# furby.net
KiCad netlist of a schematic drawn in EAGLE
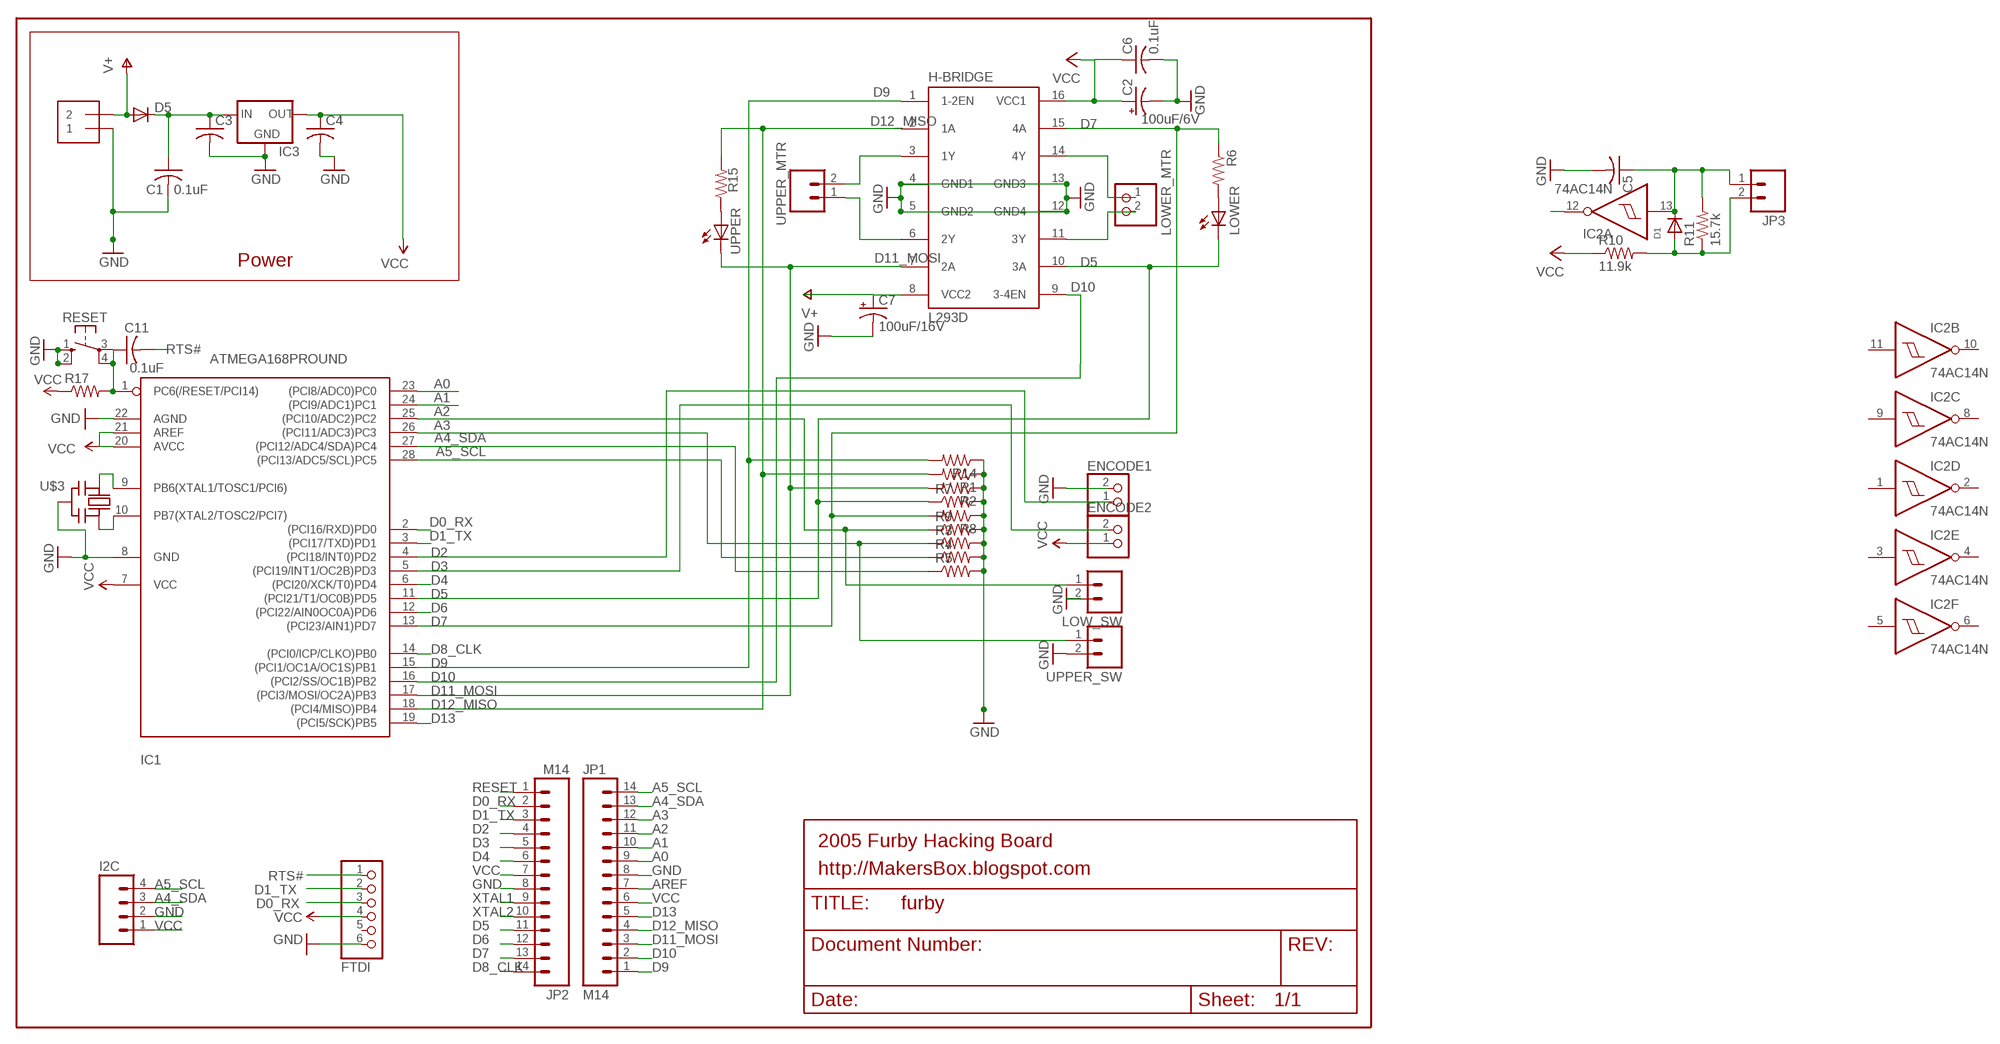
[diagram p0: schematic, sheet 1]

(export (version "E")
  (design (tool "Eeschema 10.0.6"))
  (components
    (comp (ref "C1")
      (value "0.1uF")
      (footprint "eagle-import:C025-025X050")
      (libsource (lib "eagle-import") (part "minimidi_C-US025-025X050"))
    )
    (comp (ref "C2")
      (value "100uF/6V")
      (footprint "eagle-import:E2,5-5")
      (libsource (lib "eagle-import") (part "CPOL-USE2.5-5"))
    )
    (comp (ref "C3")
      (value "C-US025-025X050")
      (footprint "eagle-import:C025-025X050")
      (libsource (lib "eagle-import") (part "C-US025-025X050"))
    )
    (comp (ref "C4")
      (value "C-US025-025X050")
      (footprint "eagle-import:C025-025X050")
      (libsource (lib "eagle-import") (part "C-US025-025X050"))
    )
    (comp (ref "C5")
      (value "C-US050-025X075")
      (footprint "eagle-import:C050-025X075")
      (libsource (lib "eagle-import") (part "C-US050-025X075"))
    )
    (comp (ref "C6")
      (value "0.1uF")
      (footprint "eagle-import:C025-025X050")
      (libsource (lib "eagle-import") (part "rcl-ez_C-US025-025X050"))
    )
    (comp (ref "C7")
      (value "100uF/16V")
      (footprint "eagle-import:E2,5-6")
      (libsource (lib "eagle-import") (part "CPOL-USE2.5-6"))
    )
    (comp (ref "C11")
      (value "0.1uF")
      (footprint "eagle-import:C025-025X050")
      (libsource (lib "eagle-import") (part "minimidi_C-US025-025X050"))
    )
    (comp (ref "D1")
      (value "DIODEDO-1N4148")
      (footprint "eagle-import:DO-1N4148")
      (libsource (lib "eagle-import") (part "DIODEDO-1N4148"))
    )
    (comp (ref "D5")
      (value "DIODE-D-5")
      (footprint "eagle-import:D-5")
      (libsource (lib "eagle-import") (part "DIODE-D-5"))
    )
    (comp (ref "ENCODE1")
      (value "JST_2PIN-THM")
      (footprint "eagle-import:JST-PH-2-THM")
      (libsource (lib "eagle-import") (part "JST_2PIN-THM"))
    )
    (comp (ref "ENCODE2")
      (value "JST_2PIN-THM")
      (footprint "eagle-import:JST-PH-2-THM")
      (libsource (lib "eagle-import") (part "JST_2PIN-THM"))
    )
    (comp (ref "FTDI")
      (value "FTDI")
      (footprint "eagle-import:1X06-CLEANBIG")
      (libsource (lib "eagle-import") (part "PINHD-1X6CB"))
    )
    (comp (ref "H-BRIDGE")
      (value "L293D")
      (footprint "eagle-import:DIL16")
      (libsource (lib "eagle-import") (part "L293E"))
    )
    (comp (ref "I2C")
      (value "M04PTH")
      (footprint "eagle-import:1X04")
      (libsource (lib "eagle-import") (part "M04PTH"))
    )
    (comp (ref "IC1")
      (value "ATMEGA168PROUND")
      (footprint "eagle-import:DIL28-3-ROUND")
      (libsource (lib "eagle-import") (part "ATMEGA168PROUND"))
    )
    (comp (ref "IC2")
      (value "74AC14N")
      (footprint "eagle-import:DIL14")
      (libsource (lib "eagle-import") (part "7414NAC"))
    )
    (comp (ref "IC3")
      (value "MCP1700INLINE")
      (footprint "eagle-import:TO92-INLINE")
      (libsource (lib "eagle-import") (part "MCP1700INLINE"))
    )
    (comp (ref "J1")
      (value "1X2-3.5MM")
      (footprint "eagle-import:1X2-3.5MM")
      (libsource (lib "eagle-import") (part "1X2-3.5MM"))
    )
    (comp (ref "JP1")
      (value "M14")
      (footprint "eagle-import:1X14")
      (libsource (lib "eagle-import") (part "M14"))
    )
    (comp (ref "JP2")
      (value "M14")
      (footprint "eagle-import:1X14")
      (libsource (lib "eagle-import") (part "M14"))
    )
    (comp (ref "JP3")
      (value "M02PTH")
      (footprint "eagle-import:1X02")
      (libsource (lib "eagle-import") (part "M02PTH"))
    )
    (comp (ref "LOWER")
      (value "LED3MM")
      (footprint "eagle-import:LED3MM")
      (libsource (lib "eagle-import") (part "LED3MM"))
    )
    (comp (ref "LOWER_MTR")
      (value "JST_2PIN-THM")
      (footprint "eagle-import:JST-PH-2-THM")
      (libsource (lib "eagle-import") (part "JST_2PIN-THM"))
    )
    (comp (ref "LOW_SW")
      (value "M02PTH")
      (footprint "eagle-import:1X02")
      (libsource (lib "eagle-import") (part "M02PTH"))
    )
    (comp (ref "R1")
      (value "R-US_0207/2V")
      (footprint "eagle-import:0207_2V")
      (libsource (lib "eagle-import") (part "R-US_0207/2V"))
    )
    (comp (ref "R2")
      (value "R-US_0207/2V")
      (footprint "eagle-import:0207_2V")
      (libsource (lib "eagle-import") (part "R-US_0207/2V"))
    )
    (comp (ref "R3")
      (value "R-US_0207/2V")
      (footprint "eagle-import:0207_2V")
      (libsource (lib "eagle-import") (part "R-US_0207/2V"))
    )
    (comp (ref "R4")
      (value "RESISTORPTH-1/6W")
      (footprint "eagle-import:1_6W-RES")
      (libsource (lib "eagle-import") (part "RESISTORPTH-1/6W"))
    )
    (comp (ref "R5")
      (value "RESISTORPTH-1/6W")
      (footprint "eagle-import:1_6W-RES")
      (libsource (lib "eagle-import") (part "RESISTORPTH-1/6W"))
    )
    (comp (ref "R6")
      (value "R-US_0207/2V")
      (footprint "eagle-import:0207_2V")
      (libsource (lib "eagle-import") (part "R-US_0207/2V"))
    )
    (comp (ref "R7")
      (value "R-US_0207/2V")
      (footprint "eagle-import:0207_2V")
      (libsource (lib "eagle-import") (part "R-US_0207/2V"))
    )
    (comp (ref "R8")
      (value "R-US_0207/2V")
      (footprint "eagle-import:0207_2V")
      (libsource (lib "eagle-import") (part "R-US_0207/2V"))
    )
    (comp (ref "R9")
      (value "R-US_0207/2V")
      (footprint "eagle-import:0207_2V")
      (libsource (lib "eagle-import") (part "R-US_0207/2V"))
    )
    (comp (ref "R10")
      (value "11.9k")
      (footprint "eagle-import:0204_7")
      (libsource (lib "eagle-import") (part "R-US_0204/7"))
    )
    (comp (ref "R11")
      (value "15.7k")
      (footprint "eagle-import:0204_7")
      (libsource (lib "eagle-import") (part "R-US_0204/7"))
    )
    (comp (ref "R14")
      (value "R-US_0207/2V")
      (footprint "eagle-import:0207_2V")
      (libsource (lib "eagle-import") (part "R-US_0207/2V"))
    )
    (comp (ref "R15")
      (value "R-US_0207/2V")
      (footprint "eagle-import:0207_2V")
      (libsource (lib "eagle-import") (part "R-US_0207/2V"))
    )
    (comp (ref "R17")
      (value "R-US_0207/2V")
      (footprint "eagle-import:0207_2V")
      (libsource (lib "eagle-import") (part "R-US_0207/2V"))
    )
    (comp (ref "RESET")
      (value "10-XX")
      (footprint "eagle-import:B3F-10XX")
      (libsource (lib "eagle-import") (part "10-XX"))
    )
    (comp (ref "U$3")
      (value "CERMOSCILL-THM")
      (footprint "eagle-import:CERM_OSC")
      (libsource (lib "eagle-import") (part "CERMOSCILL-THM"))
    )
    (comp (ref "UPPER")
      (value "LED3MM")
      (footprint "eagle-import:LED3MM")
      (libsource (lib "eagle-import") (part "LED3MM"))
    )
    (comp (ref "UPPER_MTR")
      (value "M02POLAR")
      (footprint "eagle-import:MOLEX-1X2")
      (libsource (lib "eagle-import") (part "M02POLAR"))
    )
    (comp (ref "UPPER_SW")
      (value "M02PTH")
      (footprint "eagle-import:1X02")
      (libsource (lib "eagle-import") (part "M02PTH"))
    )
  )
  (nets
    (net (code "1") (name "/A0") (class "Default")
      (node (ref "IC1") (pin "23") (pinfunction "(PCI8/ADC0)PC0_23") (pintype "bidirectional"))
      (node (ref "JP1") (pin "9") (pinfunction "9_9") (pintype "passive"))
    )
    (net (code "2") (name "/A1") (class "Default")
      (node (ref "IC1") (pin "24") (pinfunction "(PCI9/ADC1)PC1_24") (pintype "bidirectional"))
      (node (ref "JP1") (pin "10") (pinfunction "10_10") (pintype "passive"))
    )
    (net (code "3") (name "/A2") (class "Default")
      (node (ref "IC1") (pin "25") (pinfunction "(PCI10/ADC2)PC2_25") (pintype "bidirectional"))
      (node (ref "JP1") (pin "11") (pinfunction "11_11") (pintype "passive"))
      (node (ref "LOW_SW") (pin "1") (pinfunction "1_1") (pintype "passive"))
      (node (ref "R9") (pin "1") (pinfunction "1_1") (pintype "passive"))
    )
    (net (code "4") (name "/A3") (class "Default")
      (node (ref "IC1") (pin "26") (pinfunction "(PCI11/ADC3)PC3_26") (pintype "bidirectional"))
      (node (ref "JP1") (pin "12") (pinfunction "12_12") (pintype "passive"))
      (node (ref "R3") (pin "1") (pinfunction "1_1") (pintype "passive"))
      (node (ref "UPPER_SW") (pin "1") (pinfunction "1_1") (pintype "passive"))
    )
    (net (code "5") (name "/A4_SDA") (class "Default")
      (node (ref "I2C") (pin "3") (pinfunction "3_3") (pintype "passive"))
      (node (ref "IC1") (pin "27") (pinfunction "(PCI12/ADC4/SDA)PC4_27") (pintype "bidirectional"))
      (node (ref "JP1") (pin "13") (pinfunction "13_13") (pintype "passive"))
      (node (ref "R5") (pin "1") (pinfunction "1_1") (pintype "passive"))
    )
    (net (code "6") (name "/A5_SCL") (class "Default")
      (node (ref "I2C") (pin "4") (pinfunction "4_4") (pintype "passive"))
      (node (ref "IC1") (pin "28") (pinfunction "(PCI13/ADC5/SCL)PC5_28") (pintype "bidirectional"))
      (node (ref "JP1") (pin "14") (pinfunction "14_14") (pintype "passive"))
      (node (ref "R4") (pin "1") (pinfunction "1_1") (pintype "passive"))
    )
    (net (code "7") (name "/AREF") (class "Default")
      (node (ref "JP1") (pin "7") (pinfunction "7_7") (pintype "passive"))
    )
    (net (code "8") (name "/D0_RX") (class "Default")
      (node (ref "FTDI") (pin "3") (pinfunction "3_3") (pintype "passive"))
      (node (ref "IC1") (pin "2") (pinfunction "(PCI16/RXD)PD0_2") (pintype "bidirectional"))
      (node (ref "JP2") (pin "2") (pinfunction "2_2") (pintype "passive"))
    )
    (net (code "9") (name "/D1_TX") (class "Default")
      (node (ref "FTDI") (pin "2") (pinfunction "2_2") (pintype "passive"))
      (node (ref "IC1") (pin "3") (pinfunction "(PCI17/TXD)PD1_3") (pintype "bidirectional"))
      (node (ref "JP2") (pin "3") (pinfunction "3_3") (pintype "passive"))
    )
    (net (code "10") (name "/D2") (class "Default")
      (node (ref "ENCODE1") (pin "1") (pinfunction "2_1") (pintype "passive"))
      (node (ref "IC1") (pin "4") (pinfunction "(PCI18/INT0)PD2_4") (pintype "bidirectional"))
      (node (ref "JP2") (pin "4") (pinfunction "4_4") (pintype "passive"))
    )
    (net (code "11") (name "/D3") (class "Default")
      (node (ref "ENCODE2") (pin "2") (pinfunction "1_2") (pintype "passive"))
      (node (ref "IC1") (pin "5") (pinfunction "(PCI19/INT1/OC2B)PD3_5") (pintype "bidirectional"))
      (node (ref "JP2") (pin "5") (pinfunction "5_5") (pintype "passive"))
    )
    (net (code "12") (name "/D4") (class "Default")
      (node (ref "IC1") (pin "6") (pinfunction "(PCI20/XCK/T0)PD4_6") (pintype "bidirectional"))
      (node (ref "JP2") (pin "6") (pinfunction "6_6") (pintype "passive"))
    )
    (net (code "13") (name "/D5") (class "Default")
      (node (ref "H-BRIDGE") (pin "10") (pinfunction "3A_10") (pintype "input"))
      (node (ref "IC1") (pin "11") (pinfunction "(PCI21/T1/OC0B)PD5_11") (pintype "bidirectional"))
      (node (ref "JP2") (pin "11") (pinfunction "11_11") (pintype "passive"))
      (node (ref "LOWER") (pin "K") (pinfunction "C_K") (pintype "passive"))
      (node (ref "R7") (pin "1") (pinfunction "1_1") (pintype "passive"))
    )
    (net (code "14") (name "/D6") (class "Default")
      (node (ref "IC1") (pin "12") (pinfunction "(PCI22/AIN0OC0A)PD6_12") (pintype "bidirectional"))
      (node (ref "JP2") (pin "12") (pinfunction "12_12") (pintype "passive"))
    )
    (net (code "15") (name "/D7") (class "Default")
      (node (ref "H-BRIDGE") (pin "15") (pinfunction "4A_15") (pintype "input"))
      (node (ref "IC1") (pin "13") (pinfunction "(PCI23/AIN1)PD7_13") (pintype "bidirectional"))
      (node (ref "JP2") (pin "13") (pinfunction "13_13") (pintype "passive"))
      (node (ref "R6") (pin "1") (pinfunction "1_1") (pintype "passive"))
      (node (ref "R8") (pin "2") (pinfunction "2_2") (pintype "passive"))
    )
    (net (code "16") (name "/D8_CLK") (class "Default")
      (node (ref "IC1") (pin "14") (pinfunction "(PCI0/ICP/CLKO)PB0_14") (pintype "bidirectional"))
      (node (ref "JP2") (pin "14") (pinfunction "14_14") (pintype "passive"))
    )
    (net (code "17") (name "/D9") (class "Default")
      (node (ref "H-BRIDGE") (pin "1") (pinfunction "1-2EN_1") (pintype "input"))
      (node (ref "IC1") (pin "15") (pinfunction "(PCI1/OC1A/OC1S)PB1_15") (pintype "bidirectional"))
      (node (ref "JP1") (pin "1") (pinfunction "1_1") (pintype "passive"))
      (node (ref "R14") (pin "2") (pinfunction "2_2") (pintype "passive"))
    )
    (net (code "18") (name "/D10") (class "Default")
      (node (ref "H-BRIDGE") (pin "9") (pinfunction "3-4EN_9") (pintype "input"))
      (node (ref "IC1") (pin "16") (pinfunction "(PCI2/SS/OC1B)PB2_16") (pintype "bidirectional"))
      (node (ref "JP1") (pin "2") (pinfunction "2_2") (pintype "passive"))
    )
    (net (code "19") (name "/D11_MOSI") (class "Default")
      (node (ref "H-BRIDGE") (pin "7") (pinfunction "2A_7") (pintype "input"))
      (node (ref "IC1") (pin "17") (pinfunction "(PCI3/MOSI/OC2A)PB3_17") (pintype "bidirectional"))
      (node (ref "JP1") (pin "3") (pinfunction "3_3") (pintype "passive"))
      (node (ref "R2") (pin "2") (pinfunction "2_2") (pintype "passive"))
      (node (ref "UPPER") (pin "K") (pinfunction "C_K") (pintype "passive"))
    )
    (net (code "20") (name "/D12_MISO") (class "Default")
      (node (ref "H-BRIDGE") (pin "2") (pinfunction "1A_2") (pintype "input"))
      (node (ref "IC1") (pin "18") (pinfunction "(PCI4/MISO)PB4_18") (pintype "bidirectional"))
      (node (ref "JP1") (pin "4") (pinfunction "4_4") (pintype "passive"))
      (node (ref "R1") (pin "2") (pinfunction "2_2") (pintype "passive"))
      (node (ref "R15") (pin "2") (pinfunction "2_2") (pintype "passive"))
    )
    (net (code "21") (name "/D13") (class "Default")
      (node (ref "IC1") (pin "19") (pinfunction "(PCI5/SCK)PB5_19") (pintype "bidirectional"))
      (node (ref "JP1") (pin "5") (pinfunction "5_5") (pintype "passive"))
    )
    (net (code "22") (name "/RESET") (class "Default")
      (node (ref "C11") (pin "1") (pinfunction "1_1") (pintype "passive"))
      (node (ref "IC1") (pin "1") (pinfunction "PC6(/RESET/PCI14)_1") (pintype "bidirectional"))
      (node (ref "JP2") (pin "1") (pinfunction "1_1") (pintype "passive"))
      (node (ref "R17") (pin "2") (pinfunction "2_2") (pintype "passive"))
      (node (ref "RESET") (pin "3") (pinfunction "P_3") (pintype "passive"))
      (node (ref "RESET") (pin "4") (pinfunction "P1_4") (pintype "passive"))
    )
    (net (code "23") (name "/RTS#") (class "Default")
      (node (ref "C11") (pin "2") (pinfunction "2_2") (pintype "passive"))
      (node (ref "FTDI") (pin "1") (pinfunction "1_1") (pintype "passive"))
    )
    (net (code "24") (name "/XTAL1") (class "Default")
      (node (ref "IC1") (pin "9") (pinfunction "PB6(XTAL1/TOSC1/PCI6)_9") (pintype "bidirectional"))
      (node (ref "JP2") (pin "9") (pinfunction "9_9") (pintype "passive"))
      (node (ref "U$3") (pin "P$1") (pinfunction "IN_P$1") (pintype "bidirectional"))
    )
    (net (code "25") (name "/XTAL2") (class "Default")
      (node (ref "IC1") (pin "10") (pinfunction "PB7(XTAL2/TOSC2/PCI7)_10") (pintype "bidirectional"))
      (node (ref "JP2") (pin "10") (pinfunction "10_10") (pintype "passive"))
      (node (ref "U$3") (pin "P$3") (pinfunction "OUT_P$3") (pintype "bidirectional"))
    )
    (net (code "26") (name "GND") (class "Default")
      (node (ref "C1") (pin "2") (pinfunction "2_2") (pintype "passive"))
      (node (ref "C2") (pin "-") (pinfunction "-_-") (pintype "passive"))
      (node (ref "C3") (pin "2") (pinfunction "2_2") (pintype "passive"))
      (node (ref "C4") (pin "2") (pinfunction "2_2") (pintype "passive"))
      (node (ref "C5") (pin "2") (pinfunction "2_2") (pintype "passive"))
      (node (ref "C6") (pin "2") (pinfunction "2_2") (pintype "passive"))
      (node (ref "C7") (pin "-") (pinfunction "-_-") (pintype "passive"))
      (node (ref "ENCODE1") (pin "2") (pinfunction "1_2") (pintype "passive"))
      (node (ref "FTDI") (pin "6") (pinfunction "6_6") (pintype "passive"))
      (node (ref "H-BRIDGE") (pin "12") (pinfunction "GND4_12") (pintype "power_in"))
      (node (ref "H-BRIDGE") (pin "13") (pinfunction "GND3_13") (pintype "power_in"))
      (node (ref "H-BRIDGE") (pin "4") (pinfunction "GND1_4") (pintype "power_in"))
      (node (ref "H-BRIDGE") (pin "5") (pinfunction "GND2_5") (pintype "power_in"))
      (node (ref "I2C") (pin "2") (pinfunction "2_2") (pintype "passive"))
      (node (ref "IC1") (pin "22") (pinfunction "AGND_22") (pintype "bidirectional"))
      (node (ref "IC1") (pin "8") (pinfunction "GND_8") (pintype "bidirectional"))
      (node (ref "IC3") (pin "1") (pinfunction "GND_1") (pintype "input"))
      (node (ref "J1") (pin "1") (pinfunction "1_1") (pintype "passive"))
      (node (ref "JP1") (pin "8") (pinfunction "8_8") (pintype "passive"))
      (node (ref "JP2") (pin "8") (pinfunction "8_8") (pintype "passive"))
      (node (ref "LOW_SW") (pin "2") (pinfunction "2_2") (pintype "passive"))
      (node (ref "R1") (pin "1") (pinfunction "1_1") (pintype "passive"))
      (node (ref "R14") (pin "1") (pinfunction "1_1") (pintype "passive"))
      (node (ref "R2") (pin "1") (pinfunction "1_1") (pintype "passive"))
      (node (ref "R3") (pin "2") (pinfunction "2_2") (pintype "passive"))
      (node (ref "R4") (pin "2") (pinfunction "2_2") (pintype "passive"))
      (node (ref "R5") (pin "2") (pinfunction "2_2") (pintype "passive"))
      (node (ref "R7") (pin "2") (pinfunction "2_2") (pintype "passive"))
      (node (ref "R8") (pin "1") (pinfunction "1_1") (pintype "passive"))
      (node (ref "R9") (pin "2") (pinfunction "2_2") (pintype "passive"))
      (node (ref "RESET") (pin "1") (pinfunction "S_1") (pintype "passive"))
      (node (ref "RESET") (pin "2") (pinfunction "S1_2") (pintype "passive"))
      (node (ref "U$3") (pin "P$2") (pinfunction "GND_P$2") (pintype "bidirectional"))
      (node (ref "UPPER_SW") (pin "2") (pinfunction "2_2") (pintype "passive"))
    )
    (net (code "27") (name "Net-(D1-PadA)") (class "Default")
      (node (ref "D1") (pin "A") (pinfunction "A_A") (pintype "passive"))
      (node (ref "JP3") (pin "2") (pinfunction "2_2") (pintype "passive"))
      (node (ref "R10") (pin "2") (pinfunction "2_2") (pintype "passive"))
      (node (ref "R11") (pin "1") (pinfunction "1_1") (pintype "passive"))
    )
    (net (code "28") (name "Net-(H-BRIDGE-1Y)") (class "Default")
      (node (ref "H-BRIDGE") (pin "3") (pinfunction "1Y_3") (pintype "output"))
      (node (ref "UPPER_MTR") (pin "2") (pinfunction "2_2") (pintype "passive"))
    )
    (net (code "29") (name "Net-(H-BRIDGE-2Y)") (class "Default")
      (node (ref "H-BRIDGE") (pin "6") (pinfunction "2Y_6") (pintype "output"))
      (node (ref "UPPER_MTR") (pin "1") (pinfunction "1_1") (pintype "passive"))
    )
    (net (code "30") (name "Net-(H-BRIDGE-3Y)") (class "Default")
      (node (ref "H-BRIDGE") (pin "11") (pinfunction "3Y_11") (pintype "output"))
      (node (ref "LOWER_MTR") (pin "2") (pinfunction "1_2") (pintype "passive"))
    )
    (net (code "31") (name "Net-(H-BRIDGE-4Y)") (class "Default")
      (node (ref "H-BRIDGE") (pin "14") (pinfunction "4Y_14") (pintype "output"))
      (node (ref "LOWER_MTR") (pin "1") (pinfunction "2_1") (pintype "passive"))
    )
    (net (code "32") (name "Net-(IC2A-I)") (class "Default")
      (node (ref "C5") (pin "1") (pinfunction "1_1") (pintype "passive"))
      (node (ref "D1") (pin "C") (pinfunction "C_C") (pintype "passive"))
      (node (ref "IC2") (pin "13") (pinfunction "I_13") (pintype "input"))
      (node (ref "JP3") (pin "1") (pinfunction "1_1") (pintype "passive"))
      (node (ref "R11") (pin "2") (pinfunction "2_2") (pintype "passive"))
    )
    (net (code "33") (name "Net-(IC3-IN)") (class "Default")
      (node (ref "C1") (pin "1") (pinfunction "1_1") (pintype "passive"))
      (node (ref "C3") (pin "1") (pinfunction "1_1") (pintype "passive"))
      (node (ref "D5") (pin "C") (pinfunction "C_C") (pintype "passive"))
      (node (ref "IC3") (pin "2") (pinfunction "IN_2") (pintype "input"))
    )
    (net (code "34") (name "Net-(LOWER-PadA)") (class "Default")
      (node (ref "LOWER") (pin "A") (pinfunction "A_A") (pintype "passive"))
      (node (ref "R6") (pin "2") (pinfunction "2_2") (pintype "passive"))
    )
    (net (code "35") (name "Net-(R15-Pad1)") (class "Default")
      (node (ref "R15") (pin "1") (pinfunction "1_1") (pintype "passive"))
      (node (ref "UPPER") (pin "A") (pinfunction "A_A") (pintype "passive"))
    )
    (net (code "36") (name "V+") (class "Default")
      (node (ref "C7") (pin "+") (pinfunction "+_+") (pintype "passive"))
      (node (ref "D5") (pin "A") (pinfunction "A_A") (pintype "passive"))
      (node (ref "H-BRIDGE") (pin "8") (pinfunction "VCC2_8") (pintype "power_in"))
      (node (ref "J1") (pin "2") (pinfunction "2_2") (pintype "passive"))
    )
    (net (code "37") (name "VCC") (class "Default")
      (node (ref "C2") (pin "+") (pinfunction "+_+") (pintype "passive"))
      (node (ref "C4") (pin "1") (pinfunction "1_1") (pintype "passive"))
      (node (ref "C6") (pin "1") (pinfunction "1_1") (pintype "passive"))
      (node (ref "ENCODE2") (pin "1") (pinfunction "2_1") (pintype "passive"))
      (node (ref "FTDI") (pin "4") (pinfunction "4_4") (pintype "passive"))
      (node (ref "H-BRIDGE") (pin "16") (pinfunction "VCC1_16") (pintype "power_in"))
      (node (ref "I2C") (pin "1") (pinfunction "1_1") (pintype "passive"))
      (node (ref "IC1") (pin "20") (pinfunction "AVCC_20") (pintype "bidirectional"))
      (node (ref "IC1") (pin "21") (pinfunction "AREF_21") (pintype "bidirectional"))
      (node (ref "IC1") (pin "7") (pinfunction "VCC_7") (pintype "bidirectional"))
      (node (ref "IC3") (pin "3") (pinfunction "OUT_3") (pintype "passive"))
      (node (ref "JP1") (pin "6") (pinfunction "6_6") (pintype "passive"))
      (node (ref "JP2") (pin "7") (pinfunction "7_7") (pintype "passive"))
      (node (ref "R10") (pin "1") (pinfunction "1_1") (pintype "passive"))
      (node (ref "R17") (pin "1") (pinfunction "1_1") (pintype "passive"))
    )
    (net (code "38") (name "unconnected-(FTDI-Pad5)") (class "Default")
      (node (ref "FTDI") (pin "5") (pinfunction "5_5") (pintype "passive"))
    )
    (net (code "39") (name "unconnected-(IC2A-O-Pad12)") (class "Default")
      (node (ref "IC2") (pin "12") (pinfunction "O_12") (pintype "output"))
    )
    (net (code "40") (name "unconnected-(IC2B-I-Pad11)") (class "Default")
      (node (ref "IC2") (pin "11") (pinfunction "I_11") (pintype "input"))
    )
    (net (code "41") (name "unconnected-(IC2B-O-Pad10)") (class "Default")
      (node (ref "IC2") (pin "10") (pinfunction "O_10") (pintype "output"))
    )
    (net (code "42") (name "unconnected-(IC2C-I-Pad9)") (class "Default")
      (node (ref "IC2") (pin "9") (pinfunction "I_9") (pintype "input"))
    )
    (net (code "43") (name "unconnected-(IC2C-O-Pad8)") (class "Default")
      (node (ref "IC2") (pin "8") (pinfunction "O_8") (pintype "output"))
    )
    (net (code "44") (name "unconnected-(IC2D-I-Pad1)") (class "Default")
      (node (ref "IC2") (pin "1") (pinfunction "I_1") (pintype "input"))
    )
    (net (code "45") (name "unconnected-(IC2D-O-Pad2)") (class "Default")
      (node (ref "IC2") (pin "2") (pinfunction "O_2") (pintype "output"))
    )
    (net (code "46") (name "unconnected-(IC2E-I-Pad3)") (class "Default")
      (node (ref "IC2") (pin "3") (pinfunction "I_3") (pintype "input"))
    )
    (net (code "47") (name "unconnected-(IC2E-O-Pad4)") (class "Default")
      (node (ref "IC2") (pin "4") (pinfunction "O_4") (pintype "output"))
    )
    (net (code "48") (name "unconnected-(IC2F-I-Pad5)") (class "Default")
      (node (ref "IC2") (pin "5") (pinfunction "I_5") (pintype "input"))
    )
    (net (code "49") (name "unconnected-(IC2F-O-Pad6)") (class "Default")
      (node (ref "IC2") (pin "6") (pinfunction "O_6") (pintype "output"))
    )
  )
)
